# Sheet1_wiekszy.net
KiCad netlist of a schematic drawn in Altium Designer
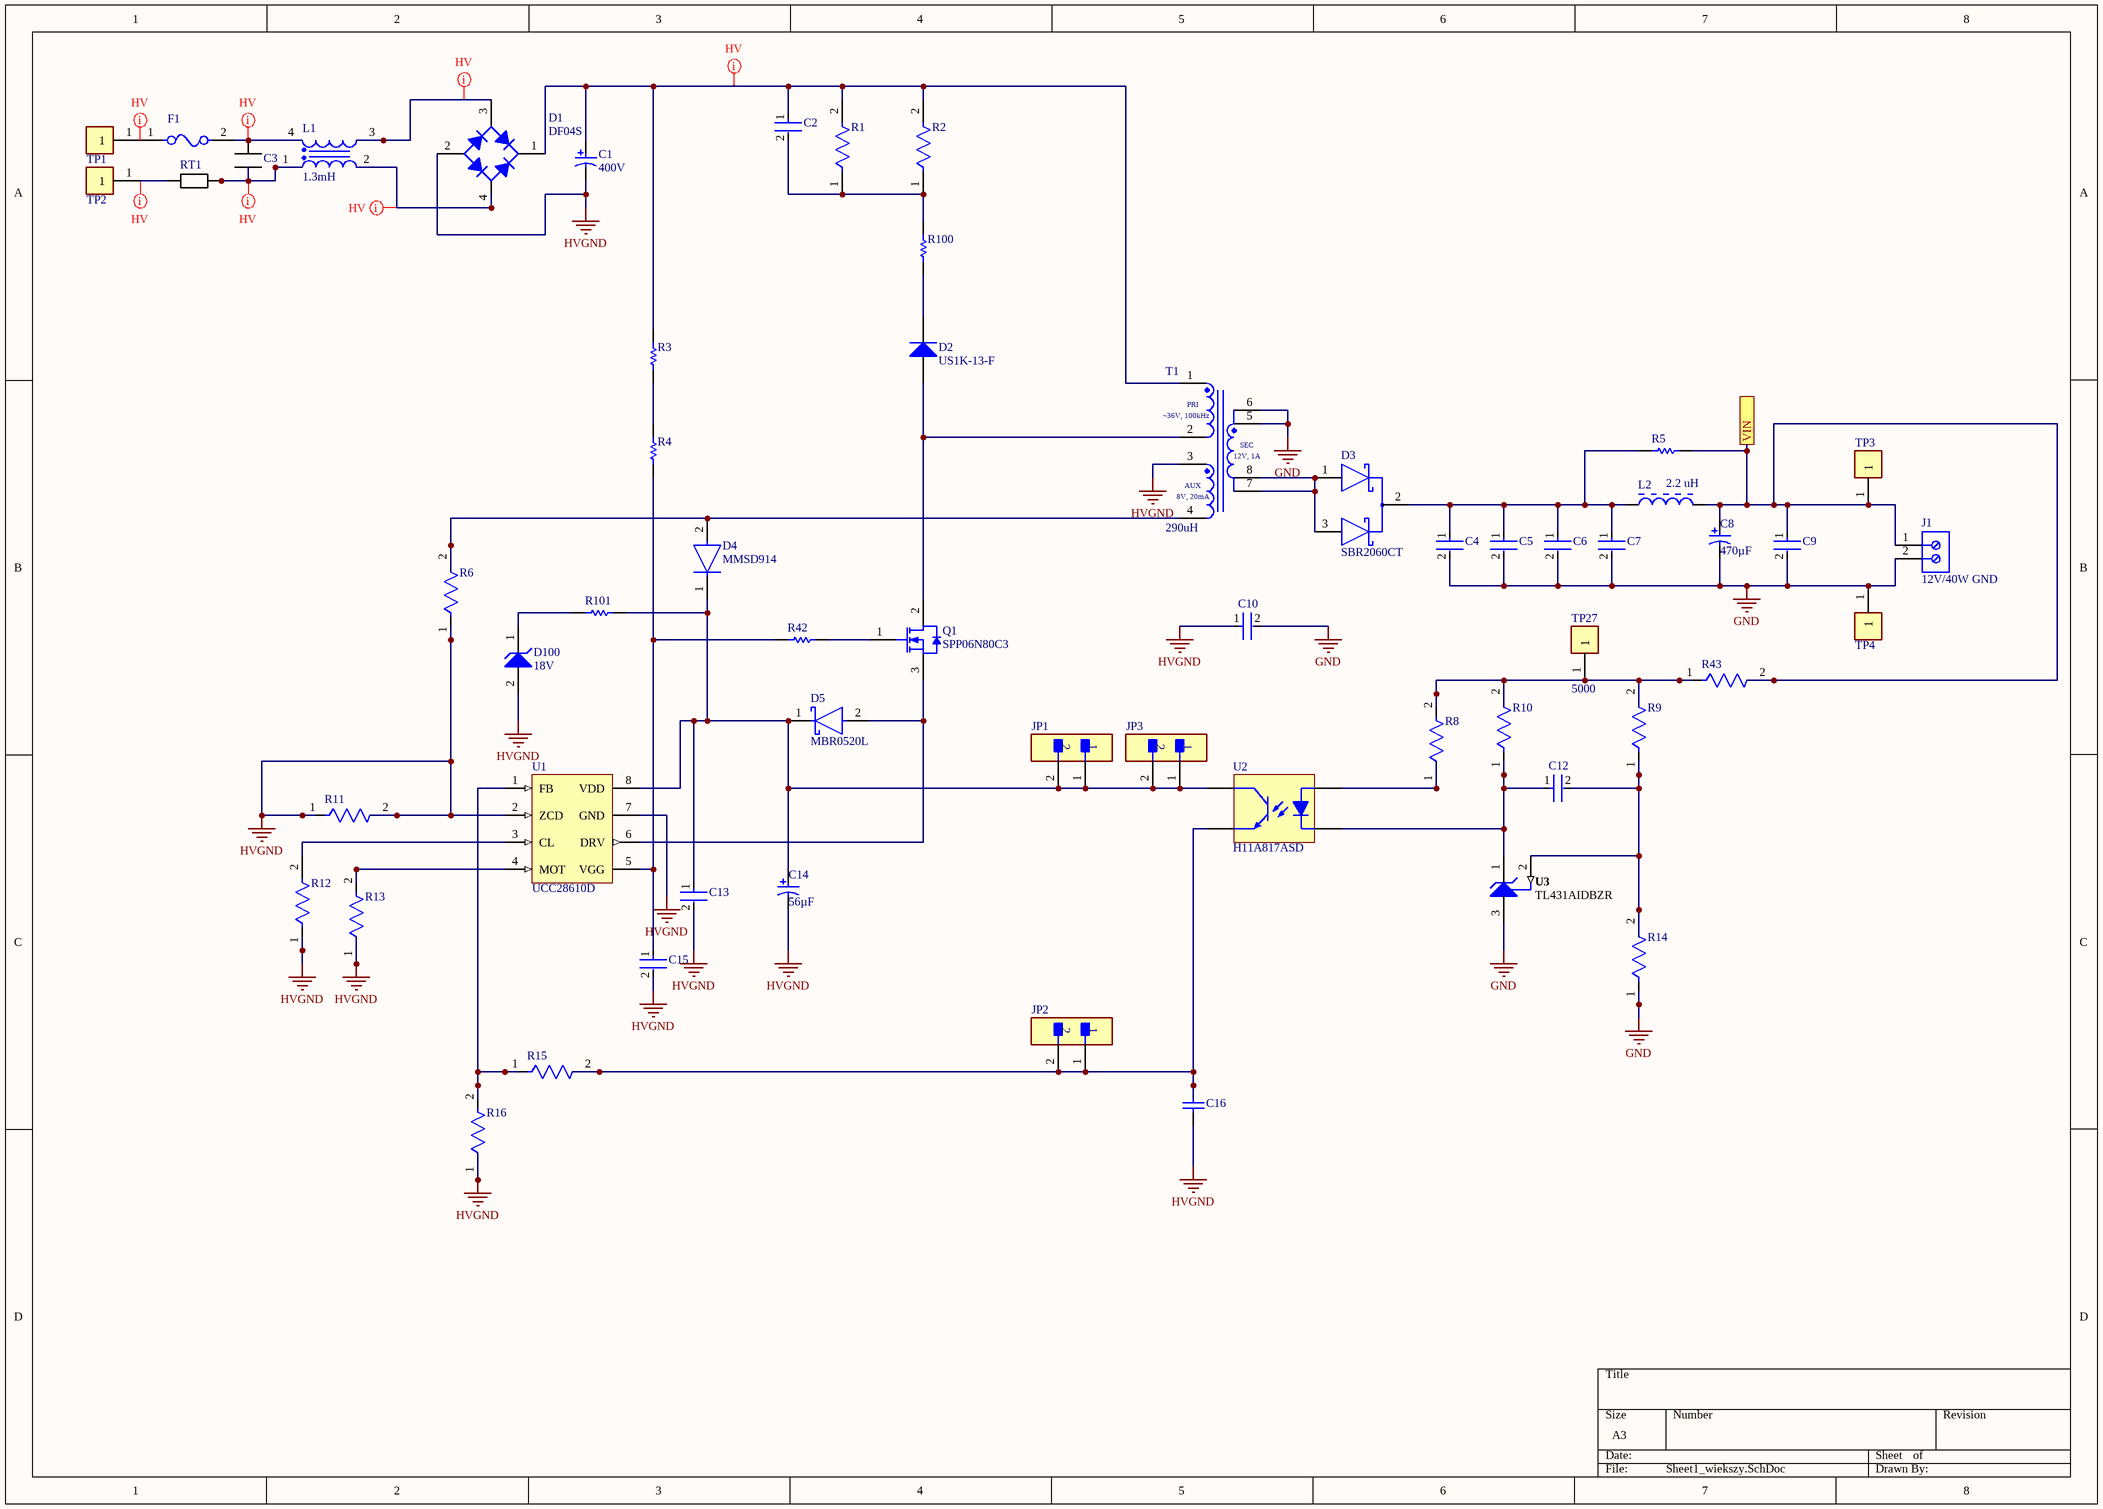
[diagram p0: Sheet1_wiekszy.SchDoc]

(export (version "E")
  (design (tool "Eeschema 10.0.6"))
  (components
    (comp (ref "C1")
      (value "400V")
      (footprint "NIC-LGU-30x30-2_V")
      (description "Aluminum Electrolytic Capacitor, 180 uF +/-20%, 400 V, -25 to 105 degC, 2-Pin THD, RoHS")
      (fields (field (name "PARTNUMBER") "LGU2G181MELB") (field (name "MANUFACTURER") "Nichicon"))
      (libsource (lib "Altium Content Vault") (part "NIC-CAP-P-2"))
    )
    (comp (ref "C2")
      (value "C1206C103K2RACTU")
      (footprint "FP-C1206C-EB-MFG")
      (description "CAP CER 10000PF 200V X7R 1206")
      (fields
        (field (name "OCTOPART") "https://octopart.com/c1206c103k2ractu-kemet-2299149")
        (field (name "MANUFACTURER") "KEMET")
      )
      (libsource (lib "Altium Content Vault") (part "b4654b650e69147ec39a6b967a45e02"))
    )
    (comp (ref "C3")
      (value "cap_0.689 x 0.217")
      (footprint "PCBComponent_1")
      (description "0.22 uF Capacitor, Film, 250VAC, 20%")
      (fields (field (name "MANUFACTURER") "Panasonic") (field (name "TOLERANCE") "20%"))
      (libsource (lib "cap_0689x0217") (part "cap_0.689 x 0.217"))
    )
    (comp (ref "C4")
      (value "1210YD226KAT2A")
      (footprint "FP-1210-L_3_3_0_4-W_2_5_0-MFG")
      (description "General Purpose Ceramic Capacitor, 1210, 22uF, 10%, X5R, 15%, 16V")
      (fields (field (name "TOLERANCE") "10%") (field (name "VOLTAGE") "16V"))
      (libsource (lib "Altium Content Vault") (part "b4654b650e69147ec39a6b967a45e02"))
    )
    (comp (ref "C5")
      (value "1210YD226KAT2A")
      (footprint "FP-1210-L_3_3_0_4-W_2_5_0-MFG")
      (description "General Purpose Ceramic Capacitor, 1210, 22uF, 10%, X5R, 15%, 16V")
      (fields (field (name "TOLERANCE") "10%") (field (name "VOLTAGE") "16V"))
      (libsource (lib "Altium Content Vault") (part "b4654b650e69147ec39a6b967a45e02"))
    )
    (comp (ref "C6")
      (value "1210YD226KAT2A")
      (footprint "FP-1210-L_3_3_0_4-W_2_5_0-MFG")
      (description "General Purpose Ceramic Capacitor, 1210, 22uF, 10%, X5R, 15%, 16V")
      (fields (field (name "TOLERANCE") "10%") (field (name "VOLTAGE") "16V"))
      (libsource (lib "Altium Content Vault") (part "b4654b650e69147ec39a6b967a45e02"))
    )
    (comp (ref "C7")
      (value "1210YD226KAT2A")
      (footprint "FP-1210-L_3_3_0_4-W_2_5_0-MFG")
      (description "General Purpose Ceramic Capacitor, 1210, 22uF, 10%, X5R, 15%, 16V")
      (fields (field (name "TOLERANCE") "10%") (field (name "VOLTAGE") "16V"))
      (libsource (lib "Altium Content Vault") (part "b4654b650e69147ec39a6b967a45e02"))
    )
    (comp (ref "C8")
      (value "EEEFK1C471P")
      (footprint "PNSC-FK-V-F_V")
      (fields (field (name "CAPACITANCE") "470µF") (field (name "MANUFACTURER") "Panasonic"))
      (libsource (lib "Altium Content Vault") (part "CAP-P-2"))
    )
    (comp (ref "C9")
      (value "C0603X104K5RACTU")
      (footprint "FP-C0603-CJ-MFG")
      (description "CAP CER 0.1UF 50V X7R 0603")
      (fields (field (name "VOLTAGE") "50V") (field (name "MANUFACTURER") "Kemet"))
      (libsource (lib "Altium Content Vault") (part "11868f565c42a9108669ba33697ecf6"))
    )
    (comp (ref "C10")
      (value "~")
      (footprint "FP-CL31-IPC_C")
      (description "Cap Ceramic 1.5nF 500V X7R ±10% SMD 1206 +125°C Embossed T/R")
      (fields (field (name "VOLTAGE") "500V") (field (name "TOLERANCE") "10%"))
      (libsource (lib "Altium Content Vault") (part "b4654b650e69147ec39a6b967a45e02"))
    )
    (comp (ref "C12")
      (value "CC0603KRX7R9BB223")
      (footprint "FP-CC0603-DA-MFG")
      (description "CAP CER 0.022UF 50V X7R 0603")
      (fields (field (name "TOLERANCE") "10%") (field (name "VOLTAGE") "50V"))
      (libsource (lib "Altium Content Vault") (part "11868f565c42a9108669ba33697ecf6"))
    )
    (comp (ref "C13")
      (value "C0603X104K5RACTU")
      (footprint "FP-C0603-CJ-MFG")
      (description "CAP CER 0.1UF 50V X7R 0603")
      (fields (field (name "VOLTAGE") "50V") (field (name "MANUFACTURER") "Kemet"))
      (libsource (lib "Altium Content Vault") (part "11868f565c42a9108669ba33697ecf6"))
    )
    (comp (ref "C14")
      (value "EEEFK1C471P")
      (footprint "PNSC-FK-V-F_V")
      (fields (field (name "CAPACITANCE") "56µF") (field (name "MANUFACTURER") "Panasonic"))
      (libsource (lib "Altium Content Vault") (part "CAP-P-2"))
    )
    (comp (ref "C15")
      (value "C0603X104K5RACTU")
      (footprint "FP-C0603-CJ-MFG")
      (description "CAP CER 0.1UF 50V X7R 0603")
      (fields (field (name "VOLTAGE") "50V") (field (name "MANUFACTURER") "Kemet"))
      (libsource (lib "Altium Content Vault") (part "11868f565c42a9108669ba33697ecf6"))
    )
    (comp (ref "C16")
      (value "GRM1885C1H101JA01D")
      (footprint "CAPC1608X90X35NL10T15")
      (fields (field (name "MANUFACTURER") "Murata"))
      (libsource (lib "Altium Content Vault") (part "CAP"))
    )
    (comp (ref "D1")
      (value "DF04S")
      (footprint "FAIR-SDIP-4_V")
      (description "Bridge Rectifier, 1.5 A, 400 V, -55 to 150 degC, 4-Pin SMD, RoHS, Tape and Reel")
      (fields (field (name "MANUFACTURER") "FairchildSemiconductor"))
      (libsource (lib "Altium Content Vault") (part "D-KACC-4"))
    )
    (comp (ref "D2")
      (value "US1K-13-F")
      (footprint "DIOD-SMA-2_A_V")
      (description "Ultra-Fast Rectifier, 1 A, 1.7 V, -65 to 150 degC, 2-Pin SMD, RoHS, Tape and Reel")
      (fields (field (name "MANUFACTURER") "Diodes Inc"))
      (libsource (lib "Altium Content Vault") (part "D-AK-2"))
    )
    (comp (ref "D3")
      (value "SBR2060CT")
      (footprint "FP-340CC-MFG")
      (description "MBR3060PT Rectifier Diode, Schottky, 1 Phase, 2 Element, 30A, 60V V(RRM), Silicon, TO-247AD")
      (libsource (lib "Altium Content Vault") (part "213139fa27cf652ab25f6c90a0a0ee5"))
    )
    (comp (ref "D4")
      (value "MMSD914")
      (footprint "FP-425-04-MFG")
      (description "MMSD914 Rectifier Diode Small Signal Switching 100V 0.2A 4ns 2-Pin SOD-123 T/R")
      (libsource (lib "Altium Content Vault") (part "d7152d700b627762746794eb795d46e"))
    )
    (comp (ref "D5")
      (value "MBR0520L")
      (footprint "FP-MA02A-MFG")
      (description "DIODE SCHOTTKY 20V 500MA SOD123")
      (libsource (lib "Altium Content Vault") (part "1d6ec82d83fb6aee721767c19dac4b9"))
    )
    (comp (ref "D100")
      (value "18V")
      (footprint "ONSC-SMB-2-403A-03_H_V")
      (description "3 W Zener Voltage Regulator, 2-Pin SMB, Tape and Reel")
      (fields (field (name "MANUFACTURER") "On Semiconductor") (field (name "PARTNUMBER") "1SMB5931BT3"))
      (libsource (lib "Altium Content Vault") (part "ONSC-K1A2-2"))
    )
    (comp (ref "F1")
      (value "0154004.DR")
      (footprint "FP-0154-MFG")
      (description "FUSE BRD MNT 4A 125VAC/VDC 2SMD")
      (fields
        (field (name "MANUFACTURER") "Littelfuse")
        (field (name "OCTOPART") "https://octopart.com/0154004.dr-littelfuse-565861")
      )
      (libsource (lib "Altium Content Vault") (part "5bcf9b9f640e542cf0359d10258e979"))
    )
    (comp (ref "J1")
      (value "12V/40W GND")
      (footprint "TECO-282836-2_V")
      (description "Female Header, Pitch 5 mm, 1 x 2 Position, Height 10 mm, Tail Length 3.5 mm, Rohs, Bulk")
      (fields (field (name "VOLTAGE") "300V") (field (name "MANUFACTURER") "TE Connectivity"))
      (libsource (lib "Altium Content Vault") (part "CN-1P-F-TB2"))
    )
    (comp (ref "JP1")
      (value "M22-2510205")
      (footprint "FP-M22-2510205-MFG")
      (description "CONN HEADER VERT 2POS 2MM")
      (fields
        (field (name "MANUFACTURER") "Harwin")
        (field (name "OCTOPART") "https://octopart.com/m22-2510205-harwin-2538221")
      )
      (libsource (lib "Altium Content Vault") (part "3bc925449376181038e59eaffc5286c"))
    )
    (comp (ref "JP2")
      (value "M22-2510205")
      (footprint "FP-M22-2510205-MFG")
      (description "CONN HEADER VERT 2POS 2MM")
      (fields
        (field (name "MANUFACTURER") "Harwin")
        (field (name "OCTOPART") "https://octopart.com/m22-2510205-harwin-2538221")
      )
      (libsource (lib "Altium Content Vault") (part "3bc925449376181038e59eaffc5286c"))
    )
    (comp (ref "JP3")
      (value "M22-2510205")
      (footprint "FP-M22-2510205-MFG")
      (description "CONN HEADER VERT 2POS 2MM")
      (fields
        (field (name "MANUFACTURER") "Harwin")
        (field (name "OCTOPART") "https://octopart.com/m22-2510205-harwin-2538221")
      )
      (libsource (lib "Altium Content Vault") (part "3bc925449376181038e59eaffc5286c"))
    )
    (comp (ref "L1")
      (value "1.3mH")
      (footprint "WE-CMB_Type XXL_L43.5W23.5H43")
      (fields (field (name "TOLERANCE") "30%"))
      (libsource (lib "Altium Content Vault") (part "WE-CMB"))
    )
    (comp (ref "L2")
      (value "RFB0807-2R2L")
      (footprint "COIL-RFB0807-2_V")
      (description "Power Inductor, 2.2 uH +/- 20%, 6 A, -40 to 125 degC, 2-Pin Radial Leaded, Dia 8.8 mm, RoHS, Tray")
      (fields
        (field (name "TOLERANCE") "+/- 20%")
        (field (name "INDUCTANCE") "2.2 uH")
        (field (name "MANUFACTURER") "Coilcraft")
      )
      (libsource (lib "Altium Content Vault") (part "COIL-IND-2A"))
    )
    (comp (ref "Q1")
      (value "SPP06N80C3")
      (footprint "INF-PG-TO220-3-1")
      (description "N-Channel CoolMOS Power-Transistor, 800 V VDS, 6 A ID, -55 to 150 degC, PG-TO220-3-1, Tube, Green")
      (fields (field (name "MANUFACTURER") "Infineon"))
      (libsource (lib "Altium Content Vault") (part "INF-NEMOS-GDS-3"))
    )
    (comp (ref "R1")
      (value "CRCW2512249KFKEG")
      (footprint "FP-CRCW2512-e3-MFG")
      (description "RES Thick Film, 249kΩ, 1%, 1W, 100ppm/°C, 2512")
      (fields (field (name "TOLERANCE") "1%"))
      (libsource (lib "Altium Content Vault") (part "1029c3af85768c4190bb7ad29bc67b5"))
    )
    (comp (ref "R2")
      (value "CRCW2512249KFKEG")
      (footprint "FP-CRCW2512-e3-MFG")
      (description "RES Thick Film, 249kΩ, 1%, 1W, 100ppm/°C, 2512")
      (fields (field (name "TOLERANCE") "1%"))
      (libsource (lib "Altium Content Vault") (part "1029c3af85768c4190bb7ad29bc67b5"))
    )
    (comp (ref "R3")
      (value "CRCW12063M00FKEA")
      (footprint "RESC3216X60X45ML10T20")
      (fields (field (name "MANUFACTURER") "Vishay Dale"))
      (libsource (lib "Altium Content Vault") (part "RES"))
    )
    (comp (ref "R4")
      (value "CRCW12063M00FKEA")
      (footprint "RESC3216X60X45ML10T20")
      (fields (field (name "MANUFACTURER") "Vishay Dale"))
      (libsource (lib "Altium Content Vault") (part "RES"))
    )
    (comp (ref "R5")
      (value "ERJ14BQFR22U")
      (footprint "RESC3225X70X50ML20T20")
      (fields (field (name "MANUFACTURER") "Panasonic"))
      (libsource (lib "Altium Content Vault") (part "RES"))
    )
    (comp (ref "R6")
      (value "RR0816P-1693-D-23D")
      (footprint "FP-RR0816-IPC_A")
      (description "169kΩ ±0.5% 0.0625W 1/16W Chip Resistor 0603 (1608 Metric) Thin Film")
      (fields (field (name "TOLERANCE") "0.5%"))
      (libsource (lib "Altium Content Vault") (part "1029c3af85768c4190bb7ad29bc67b5"))
    )
    (comp (ref "R8")
      (value "RR0816P-4991-D-68H")
      (footprint "FP-RR0816-MFG")
      (description "4.99kΩ ±0.5% 0.0625W 1/16W Chip Resistor 0603 (1608 Metric) Thin Film")
      (fields (field (name "TOLERANCE") "0.5%"))
      (libsource (lib "Altium Content Vault") (part "1029c3af85768c4190bb7ad29bc67b5"))
    )
    (comp (ref "R9")
      (value "RR0816P-103-D")
      (footprint "FP-RR0816-MFG")
      (description "10kΩ ±0.5% 0.0625W 1/16W Chip Resistor 0603 (1608 Metric) Thin Film")
      (fields (field (name "TOLERANCE") "0.5%"))
      (libsource (lib "Altium Content Vault") (part "1029c3af85768c4190bb7ad29bc67b5"))
    )
    (comp (ref "R10")
      (value "RR0816P-202-D")
      (footprint "FP-RR0816-IPC_A")
      (description "2kΩ ±0.5% 0.0625W 1/16W Chip Resistor 0603 (1608 Metric) Thin Film")
      (fields (field (name "TOLERANCE") "0.5%"))
      (libsource (lib "Altium Content Vault") (part "1029c3af85768c4190bb7ad29bc67b5"))
    )
    (comp (ref "R11")
      (value "RR0816P-4992-D-68C")
      (footprint "FP-RR0816-IPC_B")
      (description "49.9kΩ ±0.5% 0.0625W 1/16W Chip Resistor 0603 (1608 Metric) Thin Film")
      (fields (field (name "TOLERANCE") "0.5%"))
      (libsource (lib "Altium Content Vault") (part "1029c3af85768c4190bb7ad29bc67b5"))
    )
    (comp (ref "R12")
      (value "RR0816P-6042-D-76C")
      (footprint "FP-RR0816-IPC_C")
      (description "60.4kΩ ±0.5% 0.0625W 1/16W Chip Resistor 0603 (1608 Metric) Thin Film")
      (fields (field (name "TOLERANCE") "0.5%"))
      (libsource (lib "Altium Content Vault") (part "1029c3af85768c4190bb7ad29bc67b5"))
    )
    (comp (ref "R13")
      (value "RR0816P-104-D")
      (footprint "FP-RR0816-IPC_A")
      (description "100kΩ ±0.5% 0.0625W 1/16W Chip Resistor 0603 (1608 Metric) Thin Film")
      (fields (field (name "TOLERANCE") "0.5%"))
      (libsource (lib "Altium Content Vault") (part "1029c3af85768c4190bb7ad29bc67b5"))
    )
    (comp (ref "R14")
      (value "RR0816P-2611-D-41H")
      (footprint "FP-RR0816-IPC_C")
      (description "2.61kΩ ±0.5% 0.0625W 1/16W Chip Resistor 0603 (1608 Metric) Thin Film")
      (fields (field (name "TOLERANCE") "0.5%"))
      (libsource (lib "Altium Content Vault") (part "1029c3af85768c4190bb7ad29bc67b5"))
    )
    (comp (ref "R15")
      (value "RR0816P-203-D")
      (footprint "FP-RR0816-MFG")
      (description "20kΩ ±0.5% 0.0625W 1/16W Chip Resistor 0603 (1608 Metric) Thin Film")
      (fields (field (name "TOLERANCE") "0.5%"))
      (libsource (lib "Altium Content Vault") (part "1029c3af85768c4190bb7ad29bc67b5"))
    )
    (comp (ref "R16")
      (value "RR0816P-104-D")
      (footprint "FP-RR0816-IPC_A")
      (description "100kΩ ±0.5% 0.0625W 1/16W Chip Resistor 0603 (1608 Metric) Thin Film")
      (fields (field (name "TOLERANCE") "0.5%"))
      (libsource (lib "Altium Content Vault") (part "1029c3af85768c4190bb7ad29bc67b5"))
    )
    (comp (ref "R42")
      (value "CRCW08050000Z0EA")
      (footprint "RESC2013X50X30LL20T20")
      (fields (field (name "MANUFACTURER") "Vishay Dale"))
      (libsource (lib "Altium Content Vault") (part "RES"))
    )
    (comp (ref "R43")
      (value "CRCW06030000Z0EAHP")
      (footprint "FP-CRCW0603-HPe3-MFG")
      (description "RES Thick Film, 0Ω, , 0.33W, , 0603")
      (libsource (lib "Altium Content Vault") (part "1029c3af85768c4190bb7ad29bc67b5"))
    )
    (comp (ref "R100")
      (value "CRCW120651R1FKEA")
      (footprint "RESC3216X60X45NL10T20")
      (fields (field (name "MANUFACTURER") "Vishay Dale"))
      (libsource (lib "Altium Content Vault") (part "RES"))
    )
    (comp (ref "R101")
      (value "RG3216P-8200-B-T1")
      (footprint "RESC3216X50X50LL20T20")
      (fields (field (name "MANUFACTURER") "Susumu"))
      (libsource (lib "Altium Content Vault") (part "RES"))
    )
    (comp (ref "RT1")
      (value "Thermistor")
      (footprint "PCBComponent_1")
      (fields (field (name "MANUFACTURED PART NUMBER") "B57153S0479M000"))
      (libsource (lib "Schlib1_therm") (part "Thermistor"))
    )
    (comp (ref "T1")
      (value "290uH")
      (footprint "WE-FB_EP10")
      (libsource (lib "Altium Content Vault") (part "750311305"))
    )
    (comp (ref "TP1")
      (value "5000")
      (footprint "FP-5000-MFG")
      (description "PC TEST POINT MINIATURE RED")
      (libsource (lib "Altium Content Vault") (part "1e4615820a309e3ce90f9e6d957b7fa"))
    )
    (comp (ref "TP2")
      (value "5000")
      (footprint "FP-5000-MFG")
      (description "PC TEST POINT MINIATURE RED")
      (libsource (lib "Altium Content Vault") (part "1e4615820a309e3ce90f9e6d957b7fa"))
    )
    (comp (ref "TP3")
      (value "5000")
      (footprint "FP-5000-MFG")
      (description "PC TEST POINT MINIATURE RED")
      (libsource (lib "") (part "1e4615820a309e3ce90f9e6d957b7fa_2"))
    )
    (comp (ref "TP4")
      (value "5000")
      (footprint "FP-5000-MFG")
      (description "PC TEST POINT MINIATURE RED")
      (libsource (lib "") (part "1e4615820a309e3ce90f9e6d957b7fa_1"))
    )
    (comp (ref "TP27")
      (value "5000")
      (footprint "FP-5000-MFG")
      (description "PC TEST POINT MINIATURE RED")
      (libsource (lib "") (part "1e4615820a309e3ce90f9e6d957b7fa_2"))
    )
    (comp (ref "U1")
      (value "UCC28610D")
      (footprint "D0008A_N")
      (fields (field (name "MANUFACTURER") "Texas Instruments"))
      (libsource (lib "Altium Content Vault") (part "TI-UCC28610D8"))
    )
    (comp (ref "U2")
      (value "H11A817ASD")
      (footprint "FAIR-H11A817ASD-4_V")
      (description "Phototransistor, 5300 Vrms, 80% to 160% CTR, -55 to 100 degC, 4-Pin SMD, Tape and Reel")
      (fields (field (name "MANUFACTURER") "Fairchild Semiconductor"))
      (libsource (lib "Altium Content Vault") (part "FAIR-H11A817-4"))
    )
    (comp (ref "U3")
      (value "TL431AIDBZR")
      (footprint "DBZ0003A_L")
      (fields (field (name "MANUFACTURER") "Texas Instruments"))
      (libsource (lib "Altium Content Vault") (part "TI-TL431ADBZ3"))
    )
  )
  (nets
    (net (code "1") (name "/VIN") (class "Default")
      (node (ref "C8") (pin "1") (pinfunction "1_1") (pintype "passive"))
      (node (ref "C9") (pin "1") (pinfunction "1_1") (pintype "passive"))
      (node (ref "J1") (pin "1") (pinfunction "1_1") (pintype "passive"))
      (node (ref "L2") (pin "2") (pinfunction "2_2") (pintype "passive"))
      (node (ref "R43") (pin "2") (pinfunction "2_2") (pintype "passive"))
      (node (ref "R5") (pin "2") (pinfunction "2_2") (pintype "passive"))
      (node (ref "TP3") (pin "1") (pinfunction "1_1") (pintype "passive"))
    )
    (net (code "2") (name "GND") (class "Default")
      (node (ref "C10") (pin "2") (pinfunction "2_2") (pintype "passive"))
      (node (ref "C4") (pin "2") (pinfunction "2_2") (pintype "passive"))
      (node (ref "C5") (pin "2") (pinfunction "2_2") (pintype "passive"))
      (node (ref "C6") (pin "2") (pinfunction "2_2") (pintype "passive"))
      (node (ref "C7") (pin "2") (pinfunction "2_2") (pintype "passive"))
      (node (ref "C8") (pin "2") (pinfunction "2_2") (pintype "passive"))
      (node (ref "C9") (pin "2") (pinfunction "2_2") (pintype "passive"))
      (node (ref "J1") (pin "2") (pinfunction "2_2") (pintype "passive"))
      (node (ref "R14") (pin "1") (pinfunction "1_1") (pintype "passive"))
      (node (ref "T1") (pin "5") (pinfunction "5_5") (pintype "passive"))
      (node (ref "T1") (pin "6") (pinfunction "6_6") (pintype "passive"))
      (node (ref "TP4") (pin "1") (pinfunction "1_1") (pintype "passive"))
      (node (ref "U3") (pin "3") (pinfunction "ANODE_3") (pintype "passive"))
    )
    (net (code "3") (name "HVGND") (class "Default")
      (node (ref "C1") (pin "2") (pinfunction "2_2") (pintype "passive"))
      (node (ref "C10") (pin "1") (pinfunction "1_1") (pintype "passive"))
      (node (ref "C13") (pin "2") (pinfunction "2_2") (pintype "passive"))
      (node (ref "C14") (pin "2") (pinfunction "2_2") (pintype "passive"))
      (node (ref "C15") (pin "2") (pinfunction "2_2") (pintype "passive"))
      (node (ref "C16") (pin "1") (pinfunction "1_1") (pintype "passive"))
      (node (ref "D1") (pin "2") (pinfunction "A_2") (pintype "passive"))
      (node (ref "D100") (pin "2") (pinfunction "A_2") (pintype "passive"))
      (node (ref "R11") (pin "1") (pinfunction "1_1") (pintype "passive"))
      (node (ref "R11") (pin "2") (pinfunction "2_2") (pintype "passive"))
      (node (ref "R12") (pin "1") (pinfunction "1_1") (pintype "passive"))
      (node (ref "R13") (pin "1") (pinfunction "1_1") (pintype "passive"))
      (node (ref "R16") (pin "1") (pinfunction "1_1") (pintype "passive"))
      (node (ref "R6") (pin "1") (pinfunction "1_1") (pintype "passive"))
      (node (ref "T1") (pin "3") (pinfunction "3_3") (pintype "passive"))
      (node (ref "U1") (pin "2") (pinfunction "ZCD_2") (pintype "input"))
      (node (ref "U1") (pin "7") (pinfunction "GND_7") (pintype "power_in"))
    )
    (net (code "4") (name "Net-(C2-Pad2)") (class "Default")
      (node (ref "C2") (pin "2") (pinfunction "2_2") (pintype "passive"))
      (node (ref "R1") (pin "1") (pinfunction "1_1") (pintype "passive"))
      (node (ref "R100") (pin "2") (pinfunction "2_2") (pintype "passive"))
      (node (ref "R2") (pin "1") (pinfunction "1_1") (pintype "passive"))
    )
    (net (code "5") (name "Net-(C3-Pad1)") (class "Default")
      (node (ref "C3") (pin "1") (pintype "passive"))
      (node (ref "L1") (pin "1") (pinfunction "1_1") (pintype "passive"))
      (node (ref "RT1") (pin "2") (pintype "passive"))
    )
    (net (code "6") (name "Net-(C3-Pad2)") (class "Default")
      (node (ref "C3") (pin "2") (pintype "passive"))
      (node (ref "F1") (pin "2") (pinfunction "2_2") (pintype "passive"))
      (node (ref "L1") (pin "4") (pinfunction "4_4") (pintype "passive"))
    )
    (net (code "7") (name "Net-(D1-C-Pad3)") (class "Default")
      (node (ref "D1") (pin "3") (pinfunction "C_3") (pintype "passive"))
      (node (ref "L1") (pin "3") (pinfunction "3_3") (pintype "passive"))
    )
    (net (code "8") (name "Net-(D1-C-Pad4)") (class "Default")
      (node (ref "D1") (pin "4") (pinfunction "C_4") (pintype "passive"))
      (node (ref "L1") (pin "2") (pinfunction "2_2") (pintype "passive"))
    )
    (net (code "9") (name "Net-(D1-K)") (class "Default")
      (node (ref "C1") (pin "1") (pinfunction "1_1") (pintype "passive"))
      (node (ref "C2") (pin "1") (pinfunction "1_1") (pintype "passive"))
      (node (ref "D1") (pin "1") (pinfunction "K_1") (pintype "passive"))
      (node (ref "R1") (pin "2") (pinfunction "2_2") (pintype "passive"))
      (node (ref "R2") (pin "2") (pinfunction "2_2") (pintype "passive"))
      (node (ref "R3") (pin "2") (pinfunction "2_2") (pintype "passive"))
      (node (ref "T1") (pin "1") (pinfunction "1_1") (pintype "passive"))
    )
    (net (code "10") (name "Net-(D2-A)") (class "Default")
      (node (ref "D2") (pin "1") (pinfunction "A_1") (pintype "passive"))
      (node (ref "Q1") (pin "2") (pinfunction "DRAIN_2") (pintype "passive"))
      (node (ref "T1") (pin "2") (pinfunction "2_2") (pintype "passive"))
    )
    (net (code "11") (name "Net-(D2-K)") (class "Default")
      (node (ref "D2") (pin "2") (pinfunction "K_2") (pintype "passive"))
      (node (ref "R100") (pin "1") (pinfunction "1_1") (pintype "passive"))
    )
    (net (code "12") (name "Net-(D3-1_ANODE)") (class "Default")
      (node (ref "D3") (pin "1") (pinfunction "1_ANODE_1") (pintype "passive"))
      (node (ref "D3") (pin "3") (pinfunction "2_ANODE_3") (pintype "passive"))
      (node (ref "T1") (pin "7") (pinfunction "7_7") (pintype "passive"))
      (node (ref "T1") (pin "8") (pinfunction "8_8") (pintype "passive"))
    )
    (net (code "13") (name "Net-(D3-COMMON_CATHODE)") (class "Default")
      (node (ref "C4") (pin "1") (pinfunction "1_1") (pintype "passive"))
      (node (ref "C5") (pin "1") (pinfunction "1_1") (pintype "passive"))
      (node (ref "C6") (pin "1") (pinfunction "1_1") (pintype "passive"))
      (node (ref "C7") (pin "1") (pinfunction "1_1") (pintype "passive"))
      (node (ref "D3") (pin "2") (pinfunction "COMMON_CATHODE_2") (pintype "passive"))
      (node (ref "L2") (pin "1") (pinfunction "1_1") (pintype "passive"))
      (node (ref "R5") (pin "1") (pinfunction "1_1") (pintype "passive"))
    )
    (net (code "14") (name "Net-(D4-A)") (class "Default")
      (node (ref "D4") (pin "2") (pinfunction "A_2") (pintype "passive"))
      (node (ref "R6") (pin "2") (pinfunction "2_2") (pintype "passive"))
      (node (ref "T1") (pin "4") (pinfunction "4_4") (pintype "passive"))
    )
    (net (code "15") (name "Net-(D4-C)") (class "Default")
      (node (ref "C13") (pin "1") (pinfunction "1_1") (pintype "passive"))
      (node (ref "C14") (pin "1") (pinfunction "1_1") (pintype "passive"))
      (node (ref "D4") (pin "1") (pinfunction "C_1") (pintype "passive"))
      (node (ref "D5") (pin "1") (pinfunction "C_1") (pintype "passive"))
      (node (ref "JP1") (pin "1") (pinfunction "1_1") (pintype "passive"))
      (node (ref "JP1") (pin "2") (pinfunction "2_2") (pintype "passive"))
      (node (ref "JP3") (pin "1") (pinfunction "1_1") (pintype "passive"))
      (node (ref "JP3") (pin "2") (pinfunction "2_2") (pintype "passive"))
      (node (ref "R101") (pin "2") (pinfunction "2_2") (pintype "passive"))
      (node (ref "U1") (pin "8") (pinfunction "VDD_8") (pintype "power_in"))
      (node (ref "U2") (pin "4") (pinfunction "COLLECTOR_4") (pintype "passive"))
    )
    (net (code "16") (name "Net-(D5-A)") (class "Default")
      (node (ref "D5") (pin "2") (pinfunction "A_2") (pintype "passive"))
      (node (ref "Q1") (pin "3") (pinfunction "SOURCE_3") (pintype "passive"))
      (node (ref "U1") (pin "6") (pinfunction "DRV_6") (pintype "output"))
    )
    (net (code "17") (name "Net-(D100-K)") (class "Default")
      (node (ref "D100") (pin "1") (pinfunction "K_1") (pintype "passive"))
      (node (ref "R101") (pin "1") (pinfunction "1_1") (pintype "passive"))
    )
    (net (code "18") (name "Net-(F1-Pad1)") (class "Default")
      (node (ref "F1") (pin "1") (pinfunction "1_1") (pintype "passive"))
      (node (ref "TP1") (pin "1") (pinfunction "1_1") (pintype "passive"))
    )
    (net (code "19") (name "Net-(Q1-GATE)") (class "Default")
      (node (ref "Q1") (pin "1") (pinfunction "GATE_1") (pintype "passive"))
      (node (ref "R42") (pin "2") (pinfunction "2_2") (pintype "passive"))
    )
    (net (code "20") (name "Net-(R3-Pad1)") (class "Default")
      (node (ref "R3") (pin "1") (pinfunction "1_1") (pintype "passive"))
      (node (ref "R4") (pin "2") (pinfunction "2_2") (pintype "passive"))
    )
    (net (code "21") (name "Net-(R10-Pad2)") (class "Default")
      (node (ref "R10") (pin "2") (pinfunction "2_2") (pintype "passive"))
      (node (ref "R43") (pin "1") (pinfunction "1_1") (pintype "passive"))
      (node (ref "R8") (pin "2") (pinfunction "2_2") (pintype "passive"))
      (node (ref "R9") (pin "2") (pinfunction "2_2") (pintype "passive"))
      (node (ref "TP27") (pin "1") (pinfunction "1_1") (pintype "passive"))
    )
    (net (code "22") (name "Net-(RT1-Pad1)") (class "Default")
      (node (ref "RT1") (pin "1") (pintype "passive"))
      (node (ref "TP2") (pin "1") (pinfunction "1_1") (pintype "passive"))
    )
    (net (code "23") (name "Net-(U1-CL)") (class "Default")
      (node (ref "R12") (pin "2") (pinfunction "2_2") (pintype "passive"))
      (node (ref "U1") (pin "3") (pinfunction "CL_3") (pintype "input"))
    )
    (net (code "24") (name "Net-(U1-FB)") (class "Default")
      (node (ref "R15") (pin "1") (pinfunction "1_1") (pintype "passive"))
      (node (ref "R16") (pin "2") (pinfunction "2_2") (pintype "passive"))
      (node (ref "U1") (pin "1") (pinfunction "FB_1") (pintype "input"))
    )
    (net (code "25") (name "Net-(U1-MOT)") (class "Default")
      (node (ref "R13") (pin "2") (pinfunction "2_2") (pintype "passive"))
      (node (ref "U1") (pin "4") (pinfunction "MOT_4") (pintype "input"))
    )
    (net (code "26") (name "Net-(U1-VGG)") (class "Default")
      (node (ref "C15") (pin "1") (pinfunction "1_1") (pintype "passive"))
      (node (ref "R4") (pin "1") (pinfunction "1_1") (pintype "passive"))
      (node (ref "R42") (pin "1") (pinfunction "1_1") (pintype "passive"))
      (node (ref "U1") (pin "5") (pinfunction "VGG_5") (pintype "power_in"))
    )
    (net (code "27") (name "Net-(U2-ANODE)") (class "Default")
      (node (ref "R8") (pin "1") (pinfunction "1_1") (pintype "passive"))
      (node (ref "U2") (pin "1") (pinfunction "ANODE_1") (pintype "passive"))
    )
    (net (code "28") (name "Net-(U2-CATHODE)") (class "Default")
      (node (ref "C12") (pin "1") (pinfunction "1_1") (pintype "passive"))
      (node (ref "R10") (pin "1") (pinfunction "1_1") (pintype "passive"))
      (node (ref "U2") (pin "2") (pinfunction "CATHODE_2") (pintype "passive"))
      (node (ref "U3") (pin "1") (pinfunction "CATHODE_1") (pintype "passive"))
    )
    (net (code "29") (name "Net-(U2-EMITTER)") (class "Default")
      (node (ref "C16") (pin "2") (pinfunction "2_2") (pintype "passive"))
      (node (ref "JP2") (pin "1") (pinfunction "1_1") (pintype "passive"))
      (node (ref "JP2") (pin "2") (pinfunction "2_2") (pintype "passive"))
      (node (ref "R15") (pin "2") (pinfunction "2_2") (pintype "passive"))
      (node (ref "U2") (pin "3") (pinfunction "EMITTER_3") (pintype "passive"))
    )
    (net (code "30") (name "Net-(U3-REF)") (class "Default")
      (node (ref "C12") (pin "2") (pinfunction "2_2") (pintype "passive"))
      (node (ref "R14") (pin "2") (pinfunction "2_2") (pintype "passive"))
      (node (ref "R9") (pin "1") (pinfunction "1_1") (pintype "passive"))
      (node (ref "U3") (pin "2") (pinfunction "REF_2") (pintype "input"))
    )
  )
)
